# SparkFun_RedStick.net
KiCad netlist of a schematic drawn in EAGLE
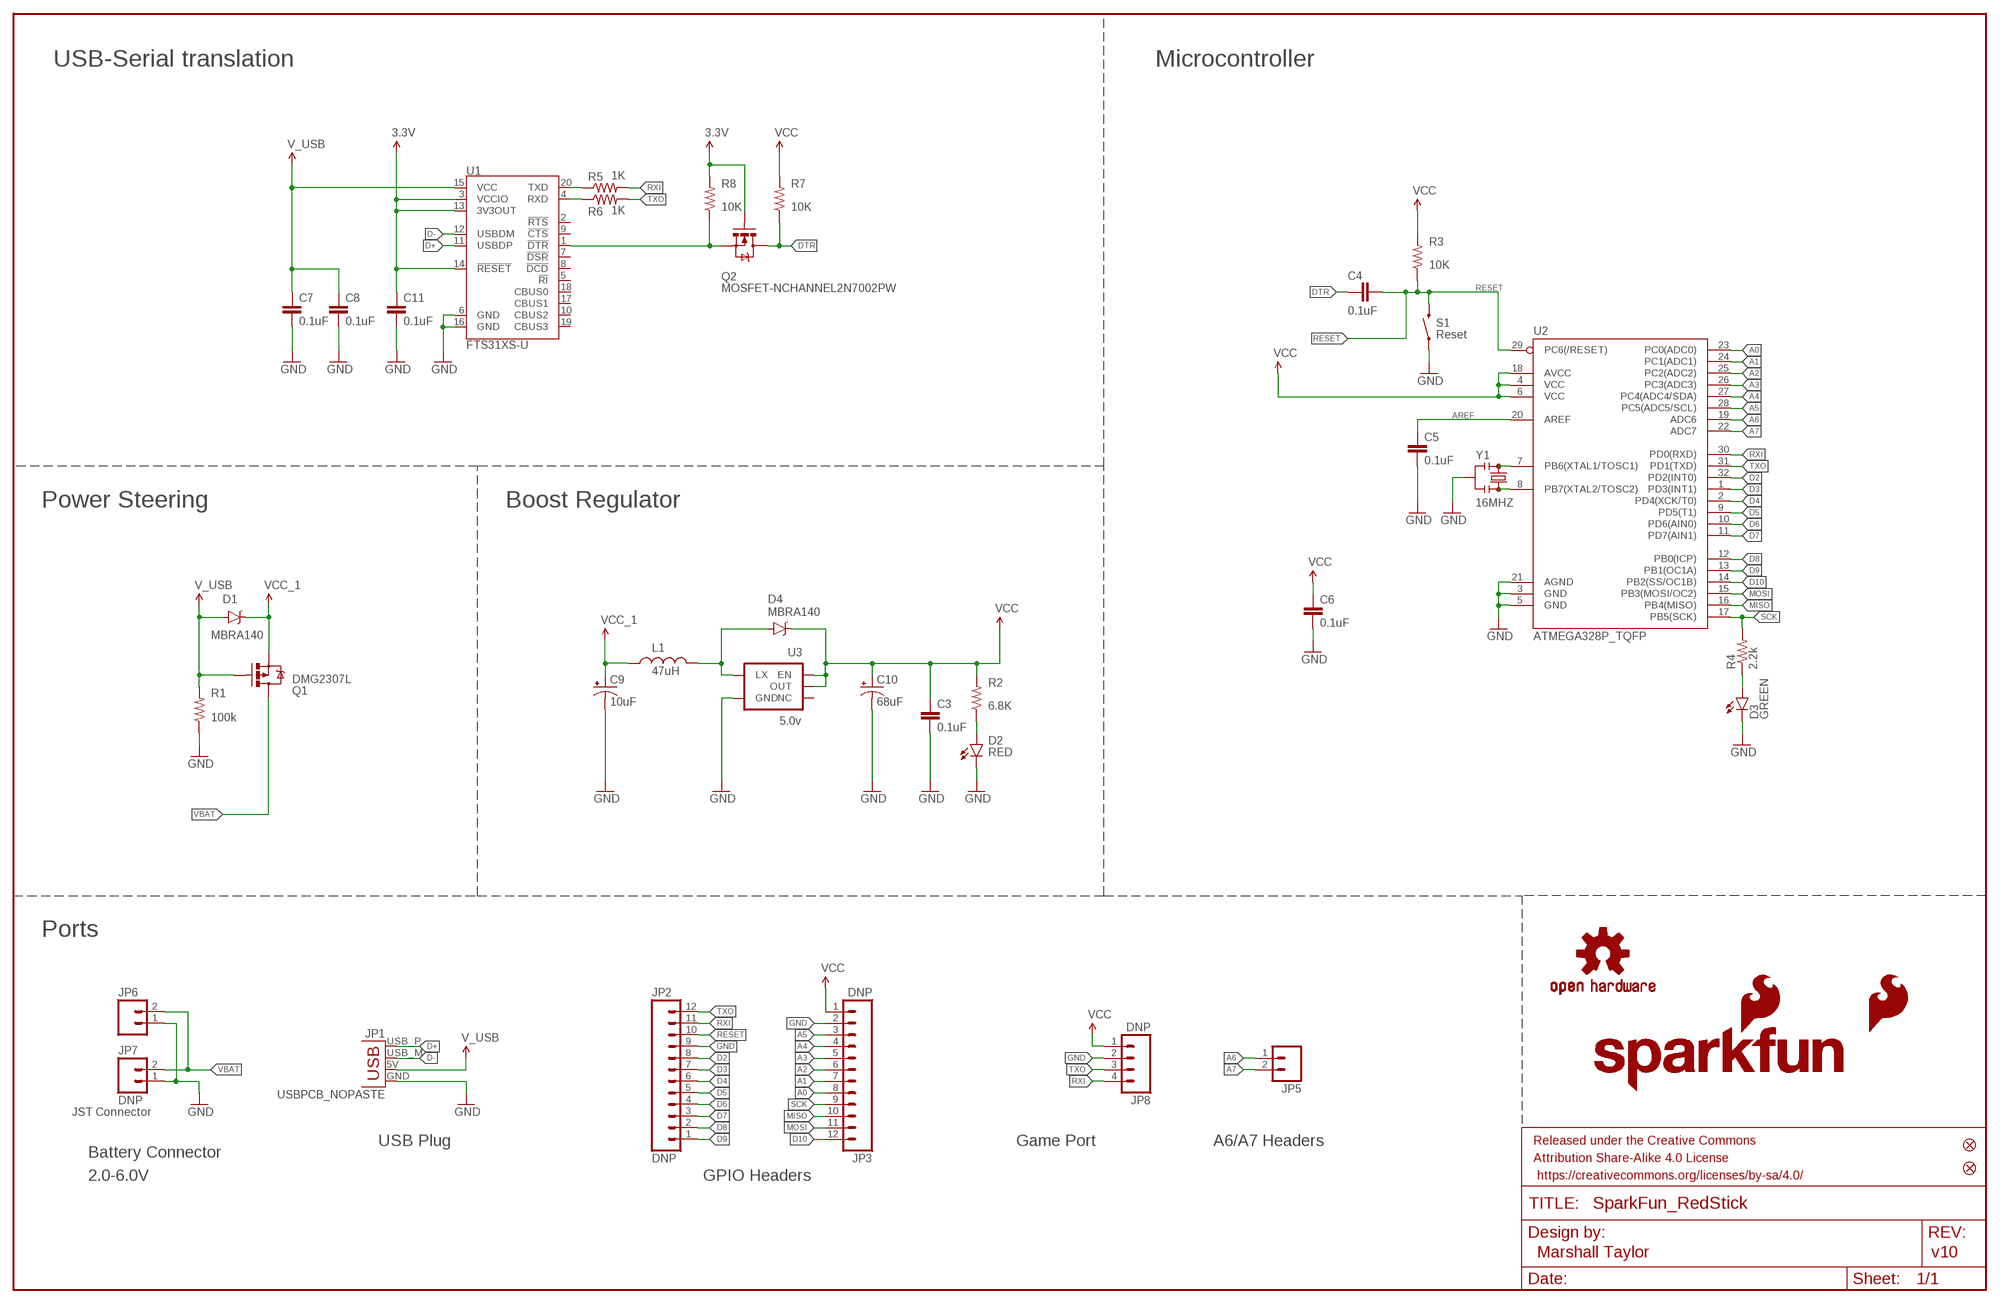
[diagram p0: schematic, sheet 1]

(export (version "E")
  (design (tool "Eeschema 10.0.6"))
  (components
    (comp (ref "C3")
      (value "0.1uF")
      (footprint "eagle-import:0603-CAP")
      (libsource (lib "eagle-import") (part "0.1UF-25V(+80/-20%)(0603)"))
    )
    (comp (ref "C4")
      (value "0.1uF")
      (footprint "eagle-import:0603-CAP")
      (libsource (lib "eagle-import") (part "0.1UF-25V(+80/-20%)(0603)"))
    )
    (comp (ref "C5")
      (value "0.1uF")
      (footprint "eagle-import:0603-CAP")
      (libsource (lib "eagle-import") (part "0.1UF-25V(+80/-20%)(0603)"))
    )
    (comp (ref "C6")
      (value "0.1uF")
      (footprint "eagle-import:0603-CAP")
      (libsource (lib "eagle-import") (part "0.1UF-25V(+80/-20%)(0603)"))
    )
    (comp (ref "C7")
      (value "0.1uF")
      (footprint "eagle-import:0603-CAP")
      (libsource (lib "eagle-import") (part "0.1UF-25V(+80/-20%)(0603)"))
    )
    (comp (ref "C8")
      (value "0.1uF")
      (footprint "eagle-import:0603-CAP")
      (libsource (lib "eagle-import") (part "0.1UF-25V(+80/-20%)(0603)"))
    )
    (comp (ref "C9")
      (value "10uF")
      (footprint "eagle-import:EIA3216")
      (libsource (lib "eagle-import") (part "10UF-16V-10%(TANT)"))
    )
    (comp (ref "C10")
      (value "68uF")
      (footprint "eagle-import:EIA3528")
      (libsource (lib "eagle-import") (part "68UF-10V-10%(TANT)"))
    )
    (comp (ref "C11")
      (value "0.1uF")
      (footprint "eagle-import:0603-CAP")
      (libsource (lib "eagle-import") (part "0.1UF-25V(+80/-20%)(0603)"))
    )
    (comp (ref "D1")
      (value "MBRA140")
      (footprint "eagle-import:SMA-DIODE")
      (libsource (lib "eagle-import") (part "DIODE-SCHOTTKY-MBRA140"))
    )
    (comp (ref "D2")
      (value "RED")
      (footprint "eagle-import:LED-0603")
      (libsource (lib "eagle-import") (part "LED-RED0603"))
    )
    (comp (ref "D3")
      (value "GREEN")
      (footprint "eagle-import:LED-0603")
      (libsource (lib "eagle-import") (part "LED-GREEN0603"))
    )
    (comp (ref "D4")
      (value "MBRA140")
      (footprint "eagle-import:SMA-DIODE")
      (libsource (lib "eagle-import") (part "DIODE-SCHOTTKY-MBRA140"))
    )
    (comp (ref "FID1")
      (value "FIDUCIAL1X2")
      (footprint "eagle-import:FIDUCIAL-1X2")
      (libsource (lib "eagle-import") (part "FIDUCIAL1X2"))
    )
    (comp (ref "FID2")
      (value "FIDUCIAL1X2")
      (footprint "eagle-import:FIDUCIAL-1X2")
      (libsource (lib "eagle-import") (part "FIDUCIAL1X2"))
    )
    (comp (ref "FRAME2")
      (value "FRAME-LEDGER")
      (footprint "eagle-import:CREATIVE_COMMONS")
      (libsource (lib "eagle-import") (part "FRAME-LEDGER"))
    )
    (comp (ref "JP1")
      (value "USBPCB_NOPASTE")
      (footprint "eagle-import:USB-A-PCB-NOPASTE")
      (libsource (lib "eagle-import") (part "USBPCB_NOPASTE"))
    )
    (comp (ref "JP2")
      (value "DNP")
      (footprint "eagle-import:1X12_NO_SILK")
      (libsource (lib "eagle-import") (part "M12NO_SILK"))
    )
    (comp (ref "JP3")
      (value "DNP")
      (footprint "eagle-import:1X12_NO_SILK")
      (libsource (lib "eagle-import") (part "M12NO_SILK"))
    )
    (comp (ref "JP5")
      (value "M021X02_NO_SILK")
      (footprint "eagle-import:1X02_NO_SILK")
      (libsource (lib "eagle-import") (part "M021X02_NO_SILK"))
    )
    (comp (ref "JP6")
      (value "M021X02_NO_SILK")
      (footprint "eagle-import:1X02_NO_SILK")
      (libsource (lib "eagle-import") (part "M021X02_NO_SILK"))
    )
    (comp (ref "JP7")
      (value "DNP")
      (footprint "eagle-import:JST-2-PTH")
      (libsource (lib "eagle-import") (part "M02JST-PTH-2"))
    )
    (comp (ref "JP8")
      (value "DNP")
      (footprint "eagle-import:1X04_NO_SILK_ALL_ROUND")
      (libsource (lib "eagle-import") (part "M04NO_SILK_ALL_ROUND"))
    )
    (comp (ref "L1")
      (value "47uH")
      (footprint "eagle-import:CR54")
      (libsource (lib "eagle-import") (part "INDUCTORCR54-47UH"))
    )
    (comp (ref "LOGO1")
      (value "SFE_LOGO_FLAME.1_INCH")
      (footprint "eagle-import:SFE_LOGO_FLAME_.1")
      (libsource (lib "eagle-import") (part "SFE_LOGO_FLAME.1_INCH"))
    )
    (comp (ref "LOGO2")
      (value "OSHW-LOGOS")
      (footprint "eagle-import:OSHW-LOGO-S")
      (libsource (lib "eagle-import") (part "OSHW-LOGOS"))
    )
    (comp (ref "Q1")
      (value "DMG2307L")
      (footprint "eagle-import:SOT23-3")
      (libsource (lib "eagle-import") (part "MOSFET-PCHANNELDMG2307L"))
    )
    (comp (ref "Q2")
      (value "MOSFET-NCHANNEL2N7002PW")
      (footprint "eagle-import:SOT323")
      (libsource (lib "eagle-import") (part "MOSFET-NCHANNEL2N7002PW"))
    )
    (comp (ref "R1")
      (value "100k")
      (footprint "eagle-import:0603-RES")
      (libsource (lib "eagle-import") (part "100KOHM-1/10W-1%(0603)"))
    )
    (comp (ref "R2")
      (value "6.8K")
      (footprint "eagle-import:0603-RES")
      (libsource (lib "eagle-import") (part "6.8KOHM1/10W1%(0603)"))
    )
    (comp (ref "R3")
      (value "10K")
      (footprint "eagle-import:0603-RES")
      (libsource (lib "eagle-import") (part "10KOHM-1/10W-1%(0603)0603"))
    )
    (comp (ref "R4")
      (value "2.2k")
      (footprint "eagle-import:0603-RES")
      (libsource (lib "eagle-import") (part "2.2KOHM-1/10W-1%(0603)"))
    )
    (comp (ref "R5")
      (value "1K")
      (footprint "eagle-import:0603-RES")
      (libsource (lib "eagle-import") (part "1KOHM-1/10W-1%(0603)"))
    )
    (comp (ref "R6")
      (value "1K")
      (footprint "eagle-import:0603-RES")
      (libsource (lib "eagle-import") (part "1KOHM-1/10W-1%(0603)"))
    )
    (comp (ref "R7")
      (value "10K")
      (footprint "eagle-import:0603-RES")
      (libsource (lib "eagle-import") (part "10KOHM-1/10W-1%(0603)0603"))
    )
    (comp (ref "R8")
      (value "10K")
      (footprint "eagle-import:0603-RES")
      (libsource (lib "eagle-import") (part "10KOHM-1/10W-1%(0603)0603"))
    )
    (comp (ref "S1")
      (value "SWITCH-MOMENTARY-2SMD-REDUNDANT")
      (footprint "eagle-import:TACTILE-SWITCH-SMD")
      (fields (field (name "FUNC") "Reset"))
      (libsource (lib "eagle-import") (part "SWITCH-MOMENTARY-2SMD-REDUNDANT"))
    )
    (comp (ref "U$1")
      (value "SFE_LOGO_NAME_FLAME.1_INCH")
      (footprint "eagle-import:SFE_LOGO_NAME_FLAME_.1")
      (libsource (lib "eagle-import") (part "SFE_LOGO_NAME_FLAME.1_INCH"))
    )
    (comp (ref "U1")
      (value "FTS31XS-U")
      (footprint "eagle-import:SSOP20_L")
      (libsource (lib "eagle-import") (part "FT231XS"))
    )
    (comp (ref "U2")
      (value "ATMEGA328P_TQFP")
      (footprint "eagle-import:TQFP32-08")
      (libsource (lib "eagle-import") (part "ATMEGA328P_TQFP"))
    )
    (comp (ref "U3")
      (value "5.0v")
      (footprint "eagle-import:SOT23-5")
      (libsource (lib "eagle-import") (part "V_REG_NCP1400_5V"))
    )
    (comp (ref "Y1")
      (value "16MHZ")
      (footprint "eagle-import:RESONATOR-SMD")
      (libsource (lib "eagle-import") (part "RESONATOR16MHZ"))
    )
  )
  (nets
    (net (code "1") (name "/AREF") (class "Default")
      (node (ref "C5") (pin "1") (pinfunction "1_1") (pintype "passive"))
      (node (ref "U2") (pin "20") (pinfunction "AREF_20") (pintype "bidirectional"))
    )
    (net (code "2") (name "3.3V") (class "Default")
      (node (ref "C11") (pin "1") (pinfunction "1_1") (pintype "passive"))
      (node (ref "Q2") (pin "1") (pinfunction "G_1") (pintype "passive"))
      (node (ref "R8") (pin "2") (pinfunction "2_2") (pintype "passive"))
      (node (ref "U1") (pin "13") (pinfunction "3V3OUT_13") (pintype "bidirectional"))
      (node (ref "U1") (pin "14") (pinfunction "~{RESET}_14") (pintype "bidirectional"))
      (node (ref "U1") (pin "3") (pinfunction "VCCIO_3") (pintype "bidirectional"))
    )
    (net (code "3") (name "A0") (class "Default")
      (node (ref "JP3") (pin "8") (pinfunction "8_8") (pintype "passive"))
      (node (ref "U2") (pin "23") (pinfunction "PC0(ADC0)_23") (pintype "bidirectional"))
    )
    (net (code "4") (name "A1") (class "Default")
      (node (ref "JP3") (pin "7") (pinfunction "7_7") (pintype "passive"))
      (node (ref "U2") (pin "24") (pinfunction "PC1(ADC1)_24") (pintype "bidirectional"))
    )
    (net (code "5") (name "A2") (class "Default")
      (node (ref "JP3") (pin "6") (pinfunction "6_6") (pintype "passive"))
      (node (ref "U2") (pin "25") (pinfunction "PC2(ADC2)_25") (pintype "bidirectional"))
    )
    (net (code "6") (name "A3") (class "Default")
      (node (ref "JP3") (pin "5") (pinfunction "5_5") (pintype "passive"))
      (node (ref "U2") (pin "26") (pinfunction "PC3(ADC3)_26") (pintype "bidirectional"))
    )
    (net (code "7") (name "A4") (class "Default")
      (node (ref "JP3") (pin "4") (pinfunction "4_4") (pintype "passive"))
      (node (ref "U2") (pin "27") (pinfunction "PC4(ADC4/SDA)_27") (pintype "bidirectional"))
    )
    (net (code "8") (name "A5") (class "Default")
      (node (ref "JP3") (pin "3") (pinfunction "3_3") (pintype "passive"))
      (node (ref "U2") (pin "28") (pinfunction "PC5(ADC5/SCL)_28") (pintype "bidirectional"))
    )
    (net (code "9") (name "A6") (class "Default")
      (node (ref "JP5") (pin "1") (pinfunction "1_1") (pintype "passive"))
      (node (ref "U2") (pin "19") (pinfunction "ADC6_19") (pintype "bidirectional"))
    )
    (net (code "10") (name "A7") (class "Default")
      (node (ref "JP5") (pin "2") (pinfunction "2_2") (pintype "passive"))
      (node (ref "U2") (pin "22") (pinfunction "ADC7_22") (pintype "bidirectional"))
    )
    (net (code "11") (name "D+") (class "Default")
      (node (ref "JP1") (pin "USB_P") (pinfunction "D+_USB_P") (pintype "bidirectional"))
      (node (ref "U1") (pin "11") (pinfunction "USBDP_11") (pintype "bidirectional"))
    )
    (net (code "12") (name "D-") (class "Default")
      (node (ref "JP1") (pin "USB_M") (pinfunction "D-_USB_M") (pintype "bidirectional"))
      (node (ref "U1") (pin "12") (pinfunction "USBDM_12") (pintype "bidirectional"))
    )
    (net (code "13") (name "D2") (class "Default")
      (node (ref "JP2") (pin "8") (pinfunction "8_8") (pintype "passive"))
      (node (ref "U2") (pin "32") (pinfunction "PD2(INT0)_32") (pintype "bidirectional"))
    )
    (net (code "14") (name "D3") (class "Default")
      (node (ref "JP2") (pin "7") (pinfunction "7_7") (pintype "passive"))
      (node (ref "U2") (pin "1") (pinfunction "PD3(INT1)_1") (pintype "bidirectional"))
    )
    (net (code "15") (name "D4") (class "Default")
      (node (ref "JP2") (pin "6") (pinfunction "6_6") (pintype "passive"))
      (node (ref "U2") (pin "2") (pinfunction "PD4(XCK/T0)_2") (pintype "bidirectional"))
    )
    (net (code "16") (name "D5") (class "Default")
      (node (ref "JP2") (pin "5") (pinfunction "5_5") (pintype "passive"))
      (node (ref "U2") (pin "9") (pinfunction "PD5(T1)_9") (pintype "bidirectional"))
    )
    (net (code "17") (name "D6") (class "Default")
      (node (ref "JP2") (pin "4") (pinfunction "4_4") (pintype "passive"))
      (node (ref "U2") (pin "10") (pinfunction "PD6(AIN0)_10") (pintype "bidirectional"))
    )
    (net (code "18") (name "D7") (class "Default")
      (node (ref "JP2") (pin "3") (pinfunction "3_3") (pintype "passive"))
      (node (ref "U2") (pin "11") (pinfunction "PD7(AIN1)_11") (pintype "bidirectional"))
    )
    (net (code "19") (name "D8") (class "Default")
      (node (ref "JP2") (pin "2") (pinfunction "2_2") (pintype "passive"))
      (node (ref "U2") (pin "12") (pinfunction "PB0(ICP)_12") (pintype "bidirectional"))
    )
    (net (code "20") (name "D9") (class "Default")
      (node (ref "JP2") (pin "1") (pinfunction "1_1") (pintype "passive"))
      (node (ref "U2") (pin "13") (pinfunction "PB1(OC1A)_13") (pintype "bidirectional"))
    )
    (net (code "21") (name "D10") (class "Default")
      (node (ref "JP3") (pin "12") (pinfunction "12_12") (pintype "passive"))
      (node (ref "U2") (pin "14") (pinfunction "PB2(SS/OC1B)_14") (pintype "bidirectional"))
    )
    (net (code "22") (name "DTR") (class "Default")
      (node (ref "C4") (pin "1") (pinfunction "1_1") (pintype "passive"))
      (node (ref "Q2") (pin "3") (pinfunction "D_3") (pintype "passive"))
      (node (ref "R7") (pin "1") (pinfunction "1_1") (pintype "passive"))
    )
    (net (code "23") (name "GND") (class "Default")
      (node (ref "C10") (pin "C") (pinfunction "-_C") (pintype "passive"))
      (node (ref "C11") (pin "2") (pinfunction "2_2") (pintype "passive"))
      (node (ref "C3") (pin "2") (pinfunction "2_2") (pintype "passive"))
      (node (ref "C5") (pin "2") (pinfunction "2_2") (pintype "passive"))
      (node (ref "C6") (pin "2") (pinfunction "2_2") (pintype "passive"))
      (node (ref "C7") (pin "2") (pinfunction "2_2") (pintype "passive"))
      (node (ref "C8") (pin "2") (pinfunction "2_2") (pintype "passive"))
      (node (ref "C9") (pin "C") (pinfunction "-_C") (pintype "passive"))
      (node (ref "D2") (pin "C") (pinfunction "C_C") (pintype "passive"))
      (node (ref "D3") (pin "C") (pinfunction "C_C") (pintype "passive"))
      (node (ref "JP1") (pin "GND") (pinfunction "GND_GND") (pintype "bidirectional"))
      (node (ref "JP2") (pin "9") (pinfunction "9_9") (pintype "passive"))
      (node (ref "JP3") (pin "2") (pinfunction "2_2") (pintype "passive"))
      (node (ref "JP6") (pin "1") (pinfunction "1_1") (pintype "passive"))
      (node (ref "JP7") (pin "1") (pinfunction "1_1") (pintype "passive"))
      (node (ref "JP8") (pin "2") (pinfunction "2_2") (pintype "passive"))
      (node (ref "R1") (pin "1") (pinfunction "1_1") (pintype "passive"))
      (node (ref "S1") (pin "1") (pinfunction "1_1") (pintype "passive"))
      (node (ref "S1") (pin "2") (pinfunction "1_2") (pintype "passive"))
      (node (ref "U1") (pin "16") (pinfunction "GND_16") (pintype "bidirectional"))
      (node (ref "U1") (pin "6") (pinfunction "GND_6") (pintype "bidirectional"))
      (node (ref "U2") (pin "21") (pinfunction "AGND_21") (pintype "bidirectional"))
      (node (ref "U2") (pin "3") (pinfunction "GND_3") (pintype "bidirectional"))
      (node (ref "U2") (pin "5") (pinfunction "GND_5") (pintype "bidirectional"))
      (node (ref "U3") (pin "4") (pinfunction "GND_4") (pintype "input"))
      (node (ref "Y1") (pin "2") (pinfunction "2_2") (pintype "passive"))
    )
    (net (code "24") (name "MISO") (class "Default")
      (node (ref "JP3") (pin "10") (pinfunction "10_10") (pintype "passive"))
      (node (ref "U2") (pin "16") (pinfunction "PB4(MISO)_16") (pintype "bidirectional"))
    )
    (net (code "25") (name "MOSI") (class "Default")
      (node (ref "JP3") (pin "11") (pinfunction "11_11") (pintype "passive"))
      (node (ref "U2") (pin "15") (pinfunction "PB3(MOSI/OC2)_15") (pintype "bidirectional"))
    )
    (net (code "26") (name "Net-(D2-PadA)") (class "Default")
      (node (ref "D2") (pin "A") (pinfunction "A_A") (pintype "passive"))
      (node (ref "R2") (pin "1") (pinfunction "1_1") (pintype "passive"))
    )
    (net (code "27") (name "Net-(D3-PadA)") (class "Default")
      (node (ref "D3") (pin "A") (pinfunction "A_A") (pintype "passive"))
      (node (ref "R4") (pin "1") (pinfunction "1_1") (pintype "passive"))
    )
    (net (code "28") (name "Net-(L1-2)") (class "Default")
      (node (ref "D4") (pin "A") (pinfunction "A_A") (pintype "passive"))
      (node (ref "L1") (pin "P$2") (pinfunction "2_P$2") (pintype "passive"))
      (node (ref "U3") (pin "5") (pinfunction "LX_5") (pintype "input"))
    )
    (net (code "29") (name "Net-(Q2-S)") (class "Default")
      (node (ref "Q2") (pin "2") (pinfunction "S_2") (pintype "passive"))
      (node (ref "R8") (pin "1") (pinfunction "1_1") (pintype "passive"))
      (node (ref "U1") (pin "1") (pinfunction "~{DTR}_1") (pintype "bidirectional"))
    )
    (net (code "30") (name "Net-(U1-RXD)") (class "Default")
      (node (ref "R6") (pin "1") (pinfunction "1_1") (pintype "passive"))
      (node (ref "U1") (pin "4") (pinfunction "RXD_4") (pintype "bidirectional"))
    )
    (net (code "31") (name "Net-(U1-TXD)") (class "Default")
      (node (ref "R5") (pin "1") (pinfunction "1_1") (pintype "passive"))
      (node (ref "U1") (pin "20") (pinfunction "TXD_20") (pintype "bidirectional"))
    )
    (net (code "32") (name "Net-(U2-PB6(XTAL1{slash}TOSC1))") (class "Default")
      (node (ref "U2") (pin "7") (pinfunction "PB6(XTAL1/TOSC1)_7") (pintype "bidirectional"))
      (node (ref "Y1") (pin "1") (pinfunction "1_1") (pintype "passive"))
    )
    (net (code "33") (name "Net-(U2-PB7(XTAL2{slash}TOSC2))") (class "Default")
      (node (ref "U2") (pin "8") (pinfunction "PB7(XTAL2/TOSC2)_8") (pintype "bidirectional"))
      (node (ref "Y1") (pin "3") (pinfunction "3_3") (pintype "passive"))
    )
    (net (code "34") (name "RESET") (class "Default")
      (node (ref "C4") (pin "2") (pinfunction "2_2") (pintype "passive"))
      (node (ref "JP2") (pin "10") (pinfunction "10_10") (pintype "passive"))
      (node (ref "R3") (pin "1") (pinfunction "1_1") (pintype "passive"))
      (node (ref "S1") (pin "3") (pinfunction "2_3") (pintype "passive"))
      (node (ref "S1") (pin "4") (pinfunction "2_4") (pintype "passive"))
      (node (ref "U2") (pin "29") (pinfunction "PC6(/RESET)_29") (pintype "bidirectional"))
    )
    (net (code "35") (name "RXI") (class "Default")
      (node (ref "JP2") (pin "11") (pinfunction "11_11") (pintype "passive"))
      (node (ref "JP8") (pin "4") (pinfunction "4_4") (pintype "passive"))
      (node (ref "R5") (pin "2") (pinfunction "2_2") (pintype "passive"))
      (node (ref "U2") (pin "30") (pinfunction "PD0(RXD)_30") (pintype "bidirectional"))
    )
    (net (code "36") (name "SCK") (class "Default")
      (node (ref "JP3") (pin "9") (pinfunction "9_9") (pintype "passive"))
      (node (ref "R4") (pin "2") (pinfunction "2_2") (pintype "passive"))
      (node (ref "U2") (pin "17") (pinfunction "PB5(SCK)_17") (pintype "bidirectional"))
    )
    (net (code "37") (name "TXO") (class "Default")
      (node (ref "JP2") (pin "12") (pinfunction "12_12") (pintype "passive"))
      (node (ref "JP8") (pin "3") (pinfunction "3_3") (pintype "passive"))
      (node (ref "R6") (pin "2") (pinfunction "2_2") (pintype "passive"))
      (node (ref "U2") (pin "31") (pinfunction "PD1(TXD)_31") (pintype "bidirectional"))
    )
    (net (code "38") (name "VBAT") (class "Default")
      (node (ref "JP6") (pin "2") (pinfunction "2_2") (pintype "passive"))
      (node (ref "JP7") (pin "2") (pinfunction "2_2") (pintype "passive"))
      (node (ref "Q1") (pin "3") (pinfunction "D_3") (pintype "passive"))
    )
    (net (code "39") (name "VCC") (class "Default")
      (node (ref "C10") (pin "A") (pinfunction "+_A") (pintype "passive"))
      (node (ref "C3") (pin "1") (pinfunction "1_1") (pintype "passive"))
      (node (ref "C6") (pin "1") (pinfunction "1_1") (pintype "passive"))
      (node (ref "D4") (pin "C") (pinfunction "C_C") (pintype "passive"))
      (node (ref "JP3") (pin "1") (pinfunction "1_1") (pintype "passive"))
      (node (ref "JP8") (pin "1") (pinfunction "1_1") (pintype "passive"))
      (node (ref "R2") (pin "2") (pinfunction "2_2") (pintype "passive"))
      (node (ref "R3") (pin "2") (pinfunction "2_2") (pintype "passive"))
      (node (ref "R7") (pin "2") (pinfunction "2_2") (pintype "passive"))
      (node (ref "U2") (pin "18") (pinfunction "AVCC_18") (pintype "bidirectional"))
      (node (ref "U2") (pin "4") (pinfunction "VCC_4") (pintype "bidirectional"))
      (node (ref "U2") (pin "6") (pinfunction "VCC_6") (pintype "bidirectional"))
      (node (ref "U3") (pin "1") (pinfunction "EN_1") (pintype "input"))
      (node (ref "U3") (pin "2") (pinfunction "OUT_2") (pintype "passive"))
    )
    (net (code "40") (name "VCC_1") (class "Default")
      (node (ref "C9") (pin "A") (pinfunction "+_A") (pintype "passive"))
      (node (ref "D1") (pin "C") (pinfunction "C_C") (pintype "passive"))
      (node (ref "L1") (pin "P$1") (pinfunction "1_P$1") (pintype "passive"))
      (node (ref "Q1") (pin "2") (pinfunction "S_2") (pintype "passive"))
    )
    (net (code "41") (name "V_USB") (class "Default")
      (node (ref "C7") (pin "1") (pinfunction "1_1") (pintype "passive"))
      (node (ref "C8") (pin "1") (pinfunction "1_1") (pintype "passive"))
      (node (ref "D1") (pin "A") (pinfunction "A_A") (pintype "passive"))
      (node (ref "JP1") (pin "5V") (pinfunction "VBUS_5V") (pintype "bidirectional"))
      (node (ref "Q1") (pin "1") (pinfunction "G_1") (pintype "passive"))
      (node (ref "R1") (pin "2") (pinfunction "2_2") (pintype "passive"))
      (node (ref "U1") (pin "15") (pinfunction "VCC_15") (pintype "bidirectional"))
    )
    (net (code "42") (name "unconnected-(U1-CBUS0-Pad18)") (class "Default")
      (node (ref "U1") (pin "18") (pinfunction "CBUS0_18") (pintype "bidirectional"))
    )
    (net (code "43") (name "unconnected-(U1-CBUS1-Pad17)") (class "Default")
      (node (ref "U1") (pin "17") (pinfunction "CBUS1_17") (pintype "bidirectional"))
    )
    (net (code "44") (name "unconnected-(U1-CBUS2-Pad10)") (class "Default")
      (node (ref "U1") (pin "10") (pinfunction "CBUS2_10") (pintype "bidirectional"))
    )
    (net (code "45") (name "unconnected-(U1-CBUS3-Pad19)") (class "Default")
      (node (ref "U1") (pin "19") (pinfunction "CBUS3_19") (pintype "bidirectional"))
    )
    (net (code "46") (name "unconnected-(U1-~{CTS}-Pad9)") (class "Default")
      (node (ref "U1") (pin "9") (pinfunction "~{CTS}_9") (pintype "bidirectional"))
    )
    (net (code "47") (name "unconnected-(U1-~{DCD}-Pad8)") (class "Default")
      (node (ref "U1") (pin "8") (pinfunction "~{DCD}_8") (pintype "bidirectional"))
    )
    (net (code "48") (name "unconnected-(U1-~{DSR}-Pad7)") (class "Default")
      (node (ref "U1") (pin "7") (pinfunction "~{DSR}_7") (pintype "bidirectional"))
    )
    (net (code "49") (name "unconnected-(U1-~{RI}-Pad5)") (class "Default")
      (node (ref "U1") (pin "5") (pinfunction "~{RI}_5") (pintype "bidirectional"))
    )
    (net (code "50") (name "unconnected-(U1-~{RTS}-Pad2)") (class "Default")
      (node (ref "U1") (pin "2") (pinfunction "~{RTS}_2") (pintype "bidirectional"))
    )
    (net (code "51") (name "unconnected-(U3-NC-Pad3)") (class "Default")
      (node (ref "U3") (pin "3") (pinfunction "NC_3") (pintype "input"))
    )
  )
)
